# BalanceCar.net
KiCad netlist of a schematic drawn in Altium Designer
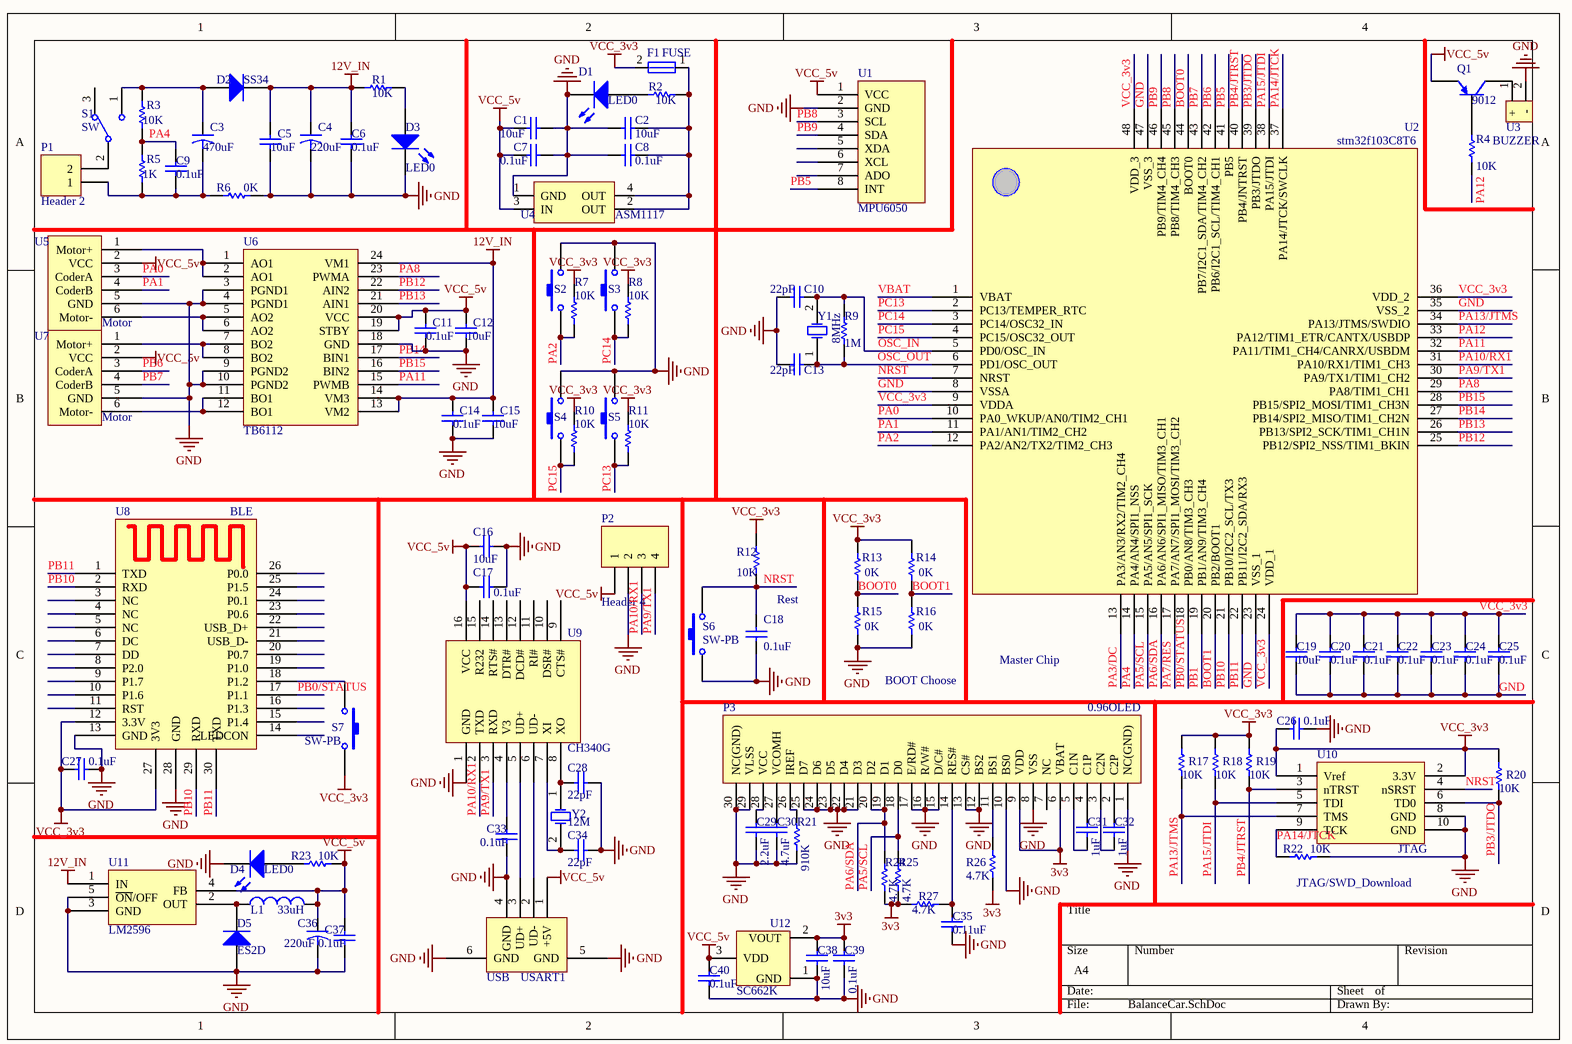
[diagram p0: BalanceCar.SchDoc]

(export (version "E")
  (design (tool "Eeschema 10.0.6"))
  (components
    (comp (ref "C1")
      (value "10uF")
      (footprint "0805")
      (description "Capacitor")
      (fields (field (name "PUBLISHER") "Altium Limited"))
      (libsource (lib "Miscellaneous Devices") (part "Cap"))
    )
    (comp (ref "C2")
      (value "10uF")
      (footprint "0805")
      (description "Capacitor")
      (fields (field (name "PUBLISHER") "Altium Limited"))
      (libsource (lib "Miscellaneous Devices") (part "Cap"))
    )
    (comp (ref "C3")
      (value "470uF")
      (footprint "SMD_8*10.5")
      (description "Capacitor")
      (fields (field (name "PUBLISHER") "Altium Limited"))
      (libsource (lib "Miscellaneous Devices") (part "Cap2"))
    )
    (comp (ref "C4")
      (value "220uF")
      (footprint "SMD_8*10.5")
      (description "Capacitor")
      (fields (field (name "PUBLISHER") "Altium Limited"))
      (libsource (lib "Miscellaneous Devices") (part "Cap2"))
    )
    (comp (ref "C5")
      (value "10uF")
      (footprint "0805")
      (description "Capacitor")
      (fields (field (name "PUBLISHER") "Altium Limited"))
      (libsource (lib "Miscellaneous Devices") (part "Cap"))
    )
    (comp (ref "C6")
      (value "0.1uF")
      (footprint "0603")
      (description "Capacitor")
      (fields (field (name "PUBLISHER") "Altium Limited"))
      (libsource (lib "Miscellaneous Devices") (part "Cap"))
    )
    (comp (ref "C7")
      (value "0.1uF")
      (footprint "0603")
      (description "Capacitor")
      (fields (field (name "PUBLISHER") "Altium Limited"))
      (libsource (lib "Miscellaneous Devices") (part "Cap"))
    )
    (comp (ref "C8")
      (value "0.1uF")
      (footprint "0603")
      (description "Capacitor")
      (fields (field (name "PUBLISHER") "Altium Limited"))
      (libsource (lib "Miscellaneous Devices") (part "Cap"))
    )
    (comp (ref "C9")
      (value "0.1uF")
      (footprint "0603")
      (description "Capacitor")
      (fields (field (name "PUBLISHER") "Altium Limited"))
      (libsource (lib "Miscellaneous Devices") (part "Cap"))
    )
    (comp (ref "C10")
      (value "22pF")
      (footprint "0603")
      (description "Capacitor")
      (fields (field (name "PUBLISHER") "Altium Limited"))
      (libsource (lib "Miscellaneous Devices") (part "Cap"))
    )
    (comp (ref "C11")
      (value "0.1uF")
      (footprint "0603")
      (description "Capacitor")
      (fields (field (name "PUBLISHER") "Altium Limited"))
      (libsource (lib "Miscellaneous Devices") (part "Cap"))
    )
    (comp (ref "C12")
      (value "10uF")
      (footprint "0805")
      (description "Capacitor")
      (fields (field (name "PUBLISHER") "Altium Limited"))
      (libsource (lib "Miscellaneous Devices") (part "Cap"))
    )
    (comp (ref "C13")
      (value "22pF")
      (footprint "0603")
      (description "Capacitor")
      (fields (field (name "PUBLISHER") "Altium Limited"))
      (libsource (lib "Miscellaneous Devices") (part "Cap"))
    )
    (comp (ref "C14")
      (value "0.1uF")
      (footprint "0603")
      (description "Capacitor")
      (fields (field (name "PUBLISHER") "Altium Limited"))
      (libsource (lib "Miscellaneous Devices") (part "Cap"))
    )
    (comp (ref "C15")
      (value "10uF")
      (footprint "0805")
      (description "Capacitor")
      (fields (field (name "PUBLISHER") "Altium Limited"))
      (libsource (lib "Miscellaneous Devices") (part "Cap"))
    )
    (comp (ref "C16")
      (value "10uF")
      (footprint "0805")
      (description "Capacitor")
      (fields (field (name "PUBLISHER") "Altium Limited"))
      (libsource (lib "Miscellaneous Devices") (part "Cap"))
    )
    (comp (ref "C17")
      (value "0.1uF")
      (footprint "0603")
      (description "Capacitor")
      (fields (field (name "PUBLISHER") "Altium Limited"))
      (libsource (lib "Miscellaneous Devices") (part "Cap"))
    )
    (comp (ref "C18")
      (value "0.1uF")
      (footprint "0603")
      (description "Capacitor")
      (fields (field (name "PUBLISHER") "Altium Limited"))
      (libsource (lib "Miscellaneous Devices") (part "Cap"))
    )
    (comp (ref "C19")
      (value "10uF")
      (footprint "0805")
      (description "Capacitor")
      (fields (field (name "PUBLISHER") "Altium Limited"))
      (libsource (lib "Miscellaneous Devices") (part "Cap"))
    )
    (comp (ref "C20")
      (value "0.1uF")
      (footprint "0603")
      (description "Capacitor")
      (fields (field (name "PUBLISHER") "Altium Limited"))
      (libsource (lib "Miscellaneous Devices") (part "Cap"))
    )
    (comp (ref "C21")
      (value "0.1uF")
      (footprint "0603")
      (description "Capacitor")
      (fields (field (name "PUBLISHER") "Altium Limited"))
      (libsource (lib "Miscellaneous Devices") (part "Cap"))
    )
    (comp (ref "C22")
      (value "0.1uF")
      (footprint "0603")
      (description "Capacitor")
      (fields (field (name "PUBLISHER") "Altium Limited"))
      (libsource (lib "Miscellaneous Devices") (part "Cap"))
    )
    (comp (ref "C23")
      (value "0.1uF")
      (footprint "0603")
      (description "Capacitor")
      (fields (field (name "PUBLISHER") "Altium Limited"))
      (libsource (lib "Miscellaneous Devices") (part "Cap"))
    )
    (comp (ref "C24")
      (value "0.1uF")
      (footprint "0603")
      (description "Capacitor")
      (fields (field (name "PUBLISHER") "Altium Limited"))
      (libsource (lib "Miscellaneous Devices") (part "Cap"))
    )
    (comp (ref "C25")
      (value "0.1uF")
      (footprint "0603")
      (description "Capacitor")
      (fields (field (name "PUBLISHER") "Altium Limited"))
      (libsource (lib "Miscellaneous Devices") (part "Cap"))
    )
    (comp (ref "C26")
      (value "0.1uF")
      (footprint "0603")
      (description "Capacitor")
      (fields (field (name "PUBLISHER") "Altium Limited"))
      (libsource (lib "Miscellaneous Devices") (part "Cap"))
    )
    (comp (ref "C27")
      (value "0.1uF")
      (footprint "0603")
      (description "Capacitor")
      (fields (field (name "PUBLISHER") "Altium Limited"))
      (libsource (lib "Miscellaneous Devices") (part "Cap"))
    )
    (comp (ref "C28")
      (value "22pF")
      (footprint "0603")
      (description "Capacitor")
      (fields (field (name "PUBLISHER") "Altium Limited"))
      (libsource (lib "Miscellaneous Devices") (part "Cap"))
    )
    (comp (ref "C29")
      (value "2.2uF")
      (footprint "0603")
      (description "Capacitor")
      (fields (field (name "PUBLISHER") "Altium Limited"))
      (libsource (lib "Miscellaneous Devices") (part "Cap"))
    )
    (comp (ref "C30")
      (value "4.7uF")
      (footprint "0603")
      (description "Capacitor")
      (fields (field (name "PUBLISHER") "Altium Limited"))
      (libsource (lib "Miscellaneous Devices") (part "Cap"))
    )
    (comp (ref "C31")
      (value "1uF")
      (footprint "0603")
      (description "Capacitor")
      (fields (field (name "PUBLISHER") "Altium Limited"))
      (libsource (lib "Miscellaneous Devices") (part "Cap"))
    )
    (comp (ref "C32")
      (value "1uF")
      (footprint "0603")
      (description "Capacitor")
      (fields (field (name "PUBLISHER") "Altium Limited"))
      (libsource (lib "Miscellaneous Devices") (part "Cap"))
    )
    (comp (ref "C33")
      (value "0.1uF")
      (footprint "0603")
      (description "Capacitor")
      (fields (field (name "PUBLISHER") "Altium Limited"))
      (libsource (lib "Miscellaneous Devices") (part "Cap"))
    )
    (comp (ref "C34")
      (value "22pF")
      (footprint "0603")
      (description "Capacitor")
      (fields (field (name "PUBLISHER") "Altium Limited"))
      (libsource (lib "Miscellaneous Devices") (part "Cap"))
    )
    (comp (ref "C35")
      (value "0.11uF")
      (footprint "0603")
      (description "Capacitor")
      (fields (field (name "PUBLISHER") "Altium Limited"))
      (libsource (lib "Miscellaneous Devices") (part "Cap"))
    )
    (comp (ref "C36")
      (value "220uF")
      (footprint "SMD_8*10.5")
      (description "Capacitor")
      (fields (field (name "PUBLISHER") "Altium Limited"))
      (libsource (lib "Miscellaneous Devices") (part "Cap2"))
    )
    (comp (ref "C37")
      (value "0.1uF")
      (footprint "0603")
      (description "Capacitor")
      (fields (field (name "PUBLISHER") "Altium Limited"))
      (libsource (lib "Miscellaneous Devices") (part "Cap"))
    )
    (comp (ref "C38")
      (value "10uF")
      (footprint "0805")
      (description "Capacitor")
      (fields (field (name "PUBLISHER") "Altium Limited"))
      (libsource (lib "Miscellaneous Devices") (part "Cap"))
    )
    (comp (ref "C39")
      (value "0.1uF")
      (footprint "0603")
      (description "Capacitor")
      (fields (field (name "PUBLISHER") "Altium Limited"))
      (libsource (lib "Miscellaneous Devices") (part "Cap"))
    )
    (comp (ref "C40")
      (value "0.1uF")
      (footprint "0603")
      (description "Capacitor")
      (fields (field (name "PUBLISHER") "Altium Limited"))
      (libsource (lib "Miscellaneous Devices") (part "Cap"))
    )
    (comp (ref "D1")
      (value "LED0")
      (footprint "LED")
      (description "Typical INFRARED GaAs LED")
      (fields (field (name "PUBLISHER") "Altium Limited"))
      (libsource (lib "Miscellaneous Devices") (part "LED0"))
    )
    (comp (ref "D2")
      (value "SS34")
      (footprint "SMA")
      (description "1 Amp General Purpose Rectifier")
      (fields (field (name "PUBLISHER") "Altium Limited"))
      (libsource (lib "Miscellaneous Devices") (part "Diode 1N4001"))
    )
    (comp (ref "D3")
      (value "LED0")
      (footprint "LED")
      (description "Typical INFRARED GaAs LED")
      (fields (field (name "PUBLISHER") "Altium Limited"))
      (libsource (lib "Miscellaneous Devices") (part "LED0"))
    )
    (comp (ref "D4")
      (value "LED0")
      (footprint "LED")
      (description "Typical INFRARED GaAs LED")
      (fields (field (name "PUBLISHER") "Altium Limited"))
      (libsource (lib "Miscellaneous Devices") (part "LED0"))
    )
    (comp (ref "D5")
      (value "ES2D")
      (footprint "SMA")
      (description "High Conductance Fast Diode")
      (fields (field (name "PUBLISHER") "Altium Limited"))
      (libsource (lib "Miscellaneous Devices") (part "Diode 1N914"))
    )
    (comp (ref "F1") (value "FUSE") (footprint "1206") (libsource (lib "BalanceCar") (part "FUSE")))
    (comp (ref "L1")
      (value "33uH")
      (footprint "CD54")
      (description "Inductor")
      (fields (field (name "PUBLISHER") "Altium Limited"))
      (libsource (lib "Miscellaneous Devices") (part "Inductor"))
    )
    (comp (ref "P1")
      (value "Header 2")
      (footprint "T")
      (description "Header, 2-Pin")
      (fields (field (name "PUBLISHER") "Altium Limited"))
      (libsource (lib "Miscellaneous Connectors") (part "Header 2"))
    )
    (comp (ref "P2")
      (value "Header 4")
      (footprint "HEADER 4PIN 2.54mm")
      (description "Header, 4-Pin")
      (fields (field (name "PUBLISHER") "Altium Limited"))
      (libsource (lib "Miscellaneous Connectors") (part "Header 4"))
    )
    (comp (ref "P3")
      (value "0.96OLED")
      (footprint "OLED")
      (description "接口")
      (fields (field (name "PUBLISHER") "Altium Limited"))
      (libsource (lib "HLW8012-Demo") (part "0.96OLED"))
    )
    (comp (ref "Q1")
      (value "9012")
      (footprint "SOP23")
      (description "PNP Bipolar Transistor")
      (fields (field (name "PUBLISHER") "Altium Limited"))
      (libsource (lib "Miscellaneous Devices") (part "PNP"))
    )
    (comp (ref "R1")
      (value "10K")
      (footprint "RES")
      (description "Resistor")
      (fields (field (name "PUBLISHER") "Altium Limited"))
      (libsource (lib "Miscellaneous Devices") (part "Res1"))
    )
    (comp (ref "R2")
      (value "10K")
      (footprint "RES")
      (description "Resistor")
      (fields (field (name "PUBLISHER") "Altium Limited"))
      (libsource (lib "Miscellaneous Devices") (part "Res1"))
    )
    (comp (ref "R3")
      (value "10K")
      (footprint "RES")
      (description "Resistor")
      (fields (field (name "PUBLISHER") "Altium Limited"))
      (libsource (lib "Miscellaneous Devices") (part "Res1"))
    )
    (comp (ref "R4")
      (value "10K")
      (footprint "RES")
      (description "Resistor")
      (fields (field (name "PUBLISHER") "Altium Limited"))
      (libsource (lib "Miscellaneous Devices") (part "Res1"))
    )
    (comp (ref "R5")
      (value "1K")
      (footprint "RES")
      (description "Resistor")
      (fields (field (name "PUBLISHER") "Altium Limited"))
      (libsource (lib "Miscellaneous Devices") (part "Res1"))
    )
    (comp (ref "R6")
      (value "0K")
      (footprint "RES")
      (description "Resistor")
      (fields (field (name "PUBLISHER") "Altium Limited"))
      (libsource (lib "Miscellaneous Devices") (part "Res1"))
    )
    (comp (ref "R7")
      (value "10K")
      (footprint "RES")
      (description "Resistor")
      (fields (field (name "PUBLISHER") "Altium Limited"))
      (libsource (lib "Miscellaneous Devices") (part "Res1"))
    )
    (comp (ref "R8")
      (value "10K")
      (footprint "RES")
      (description "Resistor")
      (fields (field (name "PUBLISHER") "Altium Limited"))
      (libsource (lib "Miscellaneous Devices") (part "Res1"))
    )
    (comp (ref "R9")
      (value "1M")
      (footprint "RES")
      (description "Resistor")
      (fields (field (name "PUBLISHER") "Altium Limited"))
      (libsource (lib "Miscellaneous Devices") (part "Res1"))
    )
    (comp (ref "R10")
      (value "10K")
      (footprint "RES")
      (description "Resistor")
      (fields (field (name "PUBLISHER") "Altium Limited"))
      (libsource (lib "Miscellaneous Devices") (part "Res1"))
    )
    (comp (ref "R11")
      (value "10K")
      (footprint "RES")
      (description "Resistor")
      (fields (field (name "PUBLISHER") "Altium Limited"))
      (libsource (lib "Miscellaneous Devices") (part "Res1"))
    )
    (comp (ref "R12")
      (value "10K")
      (footprint "RES")
      (description "Resistor")
      (fields (field (name "PUBLISHER") "Altium Limited"))
      (libsource (lib "Miscellaneous Devices") (part "Res1"))
    )
    (comp (ref "R13")
      (value "0K")
      (footprint "RES")
      (description "Resistor")
      (fields (field (name "PUBLISHER") "Altium Limited"))
      (libsource (lib "Miscellaneous Devices") (part "Res1"))
    )
    (comp (ref "R14")
      (value "0K")
      (footprint "RES")
      (description "Resistor")
      (fields (field (name "PUBLISHER") "Altium Limited"))
      (libsource (lib "Miscellaneous Devices") (part "Res1"))
    )
    (comp (ref "R15")
      (value "0K")
      (footprint "RES")
      (description "Resistor")
      (fields (field (name "PUBLISHER") "Altium Limited"))
      (libsource (lib "Miscellaneous Devices") (part "Res1"))
    )
    (comp (ref "R16")
      (value "0K")
      (footprint "RES")
      (description "Resistor")
      (fields (field (name "PUBLISHER") "Altium Limited"))
      (libsource (lib "Miscellaneous Devices") (part "Res1"))
    )
    (comp (ref "R17")
      (value "10K")
      (footprint "RES")
      (description "Resistor")
      (fields (field (name "PUBLISHER") "Altium Limited"))
      (libsource (lib "Miscellaneous Devices") (part "Res1"))
    )
    (comp (ref "R18")
      (value "10K")
      (footprint "RES")
      (description "Resistor")
      (fields (field (name "PUBLISHER") "Altium Limited"))
      (libsource (lib "Miscellaneous Devices") (part "Res1"))
    )
    (comp (ref "R19")
      (value "10K")
      (footprint "RES")
      (description "Resistor")
      (fields (field (name "PUBLISHER") "Altium Limited"))
      (libsource (lib "Miscellaneous Devices") (part "Res1"))
    )
    (comp (ref "R20")
      (value "10K")
      (footprint "RES")
      (description "Resistor")
      (fields (field (name "PUBLISHER") "Altium Limited"))
      (libsource (lib "Miscellaneous Devices") (part "Res1"))
    )
    (comp (ref "R21")
      (value "910K")
      (footprint "RES")
      (description "Resistor")
      (fields (field (name "PUBLISHER") "Altium Limited"))
      (libsource (lib "Miscellaneous Devices") (part "Res1"))
    )
    (comp (ref "R22")
      (value "10K")
      (footprint "RES")
      (description "Resistor")
      (fields (field (name "PUBLISHER") "Altium Limited"))
      (libsource (lib "Miscellaneous Devices") (part "Res1"))
    )
    (comp (ref "R23")
      (value "10K")
      (footprint "RES")
      (description "Resistor")
      (fields (field (name "PUBLISHER") "Altium Limited"))
      (libsource (lib "Miscellaneous Devices") (part "Res1"))
    )
    (comp (ref "R24")
      (value "4.7K")
      (footprint "RES")
      (description "Resistor")
      (fields (field (name "PUBLISHER") "Altium Limited"))
      (libsource (lib "Miscellaneous Devices") (part "Res1"))
    )
    (comp (ref "R25")
      (value "4.7K")
      (footprint "RES")
      (description "Resistor")
      (fields (field (name "PUBLISHER") "Altium Limited"))
      (libsource (lib "Miscellaneous Devices") (part "Res1"))
    )
    (comp (ref "R26")
      (value "4.7K")
      (footprint "RES")
      (description "Resistor")
      (fields (field (name "PUBLISHER") "Altium Limited"))
      (libsource (lib "Miscellaneous Devices") (part "Res1"))
    )
    (comp (ref "R27")
      (value "4.7K")
      (footprint "RES")
      (description "Resistor")
      (fields (field (name "PUBLISHER") "Altium Limited"))
      (libsource (lib "Miscellaneous Devices") (part "Res1"))
    )
    (comp (ref "S1")
      (value "SW")
      (footprint "MTS102")
      (description "SPDT Subminiature Toggle Switch, Right Angle Mounting, Vertical Actuation")
      (fields (field (name "PUBLISHER") "Altium Limited"))
      (libsource (lib "Miscellaneous Devices") (part "SW-SPDT"))
    )
    (comp (ref "S2")
      (value "~")
      (footprint "KEY_SOT_P2")
      (description "Switch")
      (fields (field (name "PUBLISHER") "Altium Limited"))
      (libsource (lib "Miscellaneous Devices") (part "SW-PB"))
    )
    (comp (ref "S3")
      (value "~")
      (footprint "KEY_SOT_P2")
      (description "Switch")
      (fields (field (name "PUBLISHER") "Altium Limited"))
      (libsource (lib "Miscellaneous Devices") (part "SW-PB"))
    )
    (comp (ref "S4")
      (value "~")
      (footprint "KEY_SOT_P2")
      (description "Switch")
      (fields (field (name "PUBLISHER") "Altium Limited"))
      (libsource (lib "Miscellaneous Devices") (part "SW-PB"))
    )
    (comp (ref "S5")
      (value "~")
      (footprint "KEY_SOT_P2")
      (description "Switch")
      (fields (field (name "PUBLISHER") "Altium Limited"))
      (libsource (lib "Miscellaneous Devices") (part "SW-PB"))
    )
    (comp (ref "S6")
      (value "SW-PB")
      (footprint "KEY_SOT_P2")
      (description "Switch")
      (fields (field (name "PUBLISHER") "Altium Limited"))
      (libsource (lib "Miscellaneous Devices") (part "SW-PB"))
    )
    (comp (ref "S7")
      (value "SW-PB")
      (footprint "KEY_SOT_P2")
      (description "Switch")
      (fields (field (name "PUBLISHER") "Altium Limited"))
      (libsource (lib "Miscellaneous Devices") (part "SW-PB"))
    )
    (comp (ref "U1") (value "MPU6050") (footprint "MPU6050") (libsource (lib "BalanceCar") (part "MPU6050")))
    (comp (ref "U2")
      (value "stm32f103C8T6")
      (footprint "LQFP48")
      (libsource (lib "BalanceCar") (part "stm32f103C8T6"))
    )
    (comp (ref "U3") (value "BUZZER") (footprint "BUZZER") (libsource (lib "BalanceCar") (part "BUZZER")))
    (comp (ref "U4") (value "ASM1117") (footprint "SOT-223") (libsource (lib "BalanceCar") (part "ASM1117")))
    (comp (ref "U5") (value "Motor") (footprint "Motor") (libsource (lib "BalanceCar") (part "Motor")))
    (comp (ref "U6") (value "TB6112") (footprint "SSOP24") (libsource (lib "BalanceCar") (part "TB6112")))
    (comp (ref "U7") (value "Motor") (footprint "Motor") (libsource (lib "BalanceCar") (part "Motor")))
    (comp (ref "U8") (value "BLE") (footprint "BLUETOOTH") (libsource (lib "BalanceCar") (part "BLE")))
    (comp (ref "U9") (value "CH340G") (footprint "SOP-16") (libsource (lib "Schlib1") (part "CH340G")))
    (comp (ref "U10")
      (value "JTAG")
      (footprint "HEADER 2x5 2mm")
      (libsource (lib "Boat_CorePCB") (part "JTAG"))
    )
    (comp (ref "U11") (value "LM2596") (footprint "TO263-5") (libsource (lib "BalanceCar") (part "LM2596")))
    (comp (ref "U12") (value "SC662K") (footprint "SOP23") (libsource (lib "BalanceCar") (part "SC662K")))
    (comp (ref "USART1") (value "USB") (footprint "Micro_USB") (libsource (lib "Schlib1") (part "USB")))
    (comp (ref "Y1")
      (value "8MHz")
      (footprint "HC-49S")
      (description "Crystal Oscillator")
      (fields (field (name "PUBLISHER") "Altium Limited"))
      (libsource (lib "Miscellaneous Devices") (part "XTAL"))
    )
    (comp (ref "Y2")
      (value "12M")
      (footprint "HC-49S")
      (description "Crystal Oscillator")
      (fields (field (name "PUBLISHER") "Altium Limited"))
      (libsource (lib "Miscellaneous Devices") (part "XTAL"))
    )
  )
  (nets
    (net (code "1") (name "/BOOT0") (class "Default")
      (node (ref "R13") (pin "1") (pinfunction "1_1") (pintype "passive"))
      (node (ref "R15") (pin "2") (pinfunction "2_2") (pintype "passive"))
      (node (ref "U2") (pin "44") (pinfunction "BOOT0_44") (pintype "passive"))
    )
    (net (code "2") (name "/BOOT1") (class "Default")
      (node (ref "R14") (pin "1") (pinfunction "1_1") (pintype "passive"))
      (node (ref "R16") (pin "2") (pinfunction "2_2") (pintype "passive"))
      (node (ref "U2") (pin "20") (pinfunction "PB2/BOOT1_20") (pintype "passive"))
    )
    (net (code "3") (name "/NRST") (class "Default")
      (node (ref "C18") (pin "2") (pinfunction "2_2") (pintype "passive"))
      (node (ref "R12") (pin "1") (pinfunction "1_1") (pintype "passive"))
      (node (ref "S6") (pin "2") (pinfunction "2_2") (pintype "passive"))
      (node (ref "U10") (pin "4") (pinfunction "nSRST_4") (pintype "passive"))
      (node (ref "U2") (pin "7") (pinfunction "NRST_7") (pintype "passive"))
    )
    (net (code "4") (name "/OSC_IN") (class "Default")
      (node (ref "C10") (pin "2") (pinfunction "2_2") (pintype "passive"))
      (node (ref "R9") (pin "2") (pinfunction "2_2") (pintype "passive"))
      (node (ref "U2") (pin "5") (pinfunction "PD0/OSC_IN_5") (pintype "passive"))
      (node (ref "Y1") (pin "2") (pinfunction "OSC2_2") (pintype "passive"))
    )
    (net (code "5") (name "/OSC_OUT") (class "Default")
      (node (ref "C13") (pin "2") (pinfunction "2_2") (pintype "passive"))
      (node (ref "R9") (pin "1") (pinfunction "1_1") (pintype "passive"))
      (node (ref "U2") (pin "6") (pinfunction "PD1/OSC_OUT_6") (pintype "passive"))
      (node (ref "Y1") (pin "1") (pinfunction "OSC1_1") (pintype "passive"))
    )
    (net (code "6") (name "/PA0") (class "Default")
      (node (ref "U2") (pin "10") (pinfunction "PA0_WKUP/AN0/TIM2_CH1_10") (pintype "passive"))
      (node (ref "U5") (pin "3") (pinfunction "CoderA_3") (pintype "passive"))
    )
    (net (code "7") (name "/PA1") (class "Default")
      (node (ref "U2") (pin "11") (pinfunction "PA1/AN1/TIM2_CH2_11") (pintype "passive"))
      (node (ref "U5") (pin "4") (pinfunction "CoderB_4") (pintype "passive"))
    )
    (net (code "8") (name "/PA2") (class "Default")
      (node (ref "R7") (pin "1") (pinfunction "1_1") (pintype "passive"))
      (node (ref "S2") (pin "1") (pinfunction "1_1") (pintype "passive"))
      (node (ref "U2") (pin "12") (pinfunction "PA2/AN2/TX2/TIM2_CH3_12") (pintype "passive"))
    )
    (net (code "9") (name "/PA3{slash}DC") (class "Default")
      (node (ref "U2") (pin "13") (pinfunction "PA3/AN3/RX2/TIM2_CH4_13") (pintype "passive"))
    )
    (net (code "10") (name "/PA4") (class "Default")
      (node (ref "C9") (pin "2") (pinfunction "2_2") (pintype "passive"))
      (node (ref "R3") (pin "1") (pinfunction "1_1") (pintype "passive"))
      (node (ref "R5") (pin "2") (pinfunction "2_2") (pintype "passive"))
      (node (ref "U2") (pin "14") (pinfunction "PA4/AN4/SPI1_NSS_14") (pintype "passive"))
    )
    (net (code "11") (name "/PA5{slash}SCL") (class "Default")
      (node (ref "P3") (pin "18") (pinfunction "D0_18") (pintype "passive"))
      (node (ref "R25") (pin "1") (pinfunction "1_1") (pintype "passive"))
      (node (ref "U2") (pin "15") (pinfunction "PA5/AN5/SPI1_SCK_15") (pintype "passive"))
    )
    (net (code "12") (name "/PA6{slash}SDA") (class "Default")
      (node (ref "P3") (pin "19") (pinfunction "D1_19") (pintype "passive"))
      (node (ref "P3") (pin "20") (pinfunction "D2_20") (pintype "passive"))
      (node (ref "R24") (pin "1") (pinfunction "1_1") (pintype "passive"))
      (node (ref "U2") (pin "16") (pinfunction "PA6/AN6/SPI1_MISO/TIM3_CH1_16") (pintype "passive"))
    )
    (net (code "13") (name "/PA7{slash}RES") (class "Default")
      (node (ref "U2") (pin "17") (pinfunction "PA7/AN7/SPI1_MOSI/TIM3_CH2_17") (pintype "passive"))
    )
    (net (code "14") (name "/PA8") (class "Default")
      (node (ref "U2") (pin "29") (pinfunction "PA8/TIM1_CH1_29") (pintype "passive"))
      (node (ref "U6") (pin "23") (pinfunction "PWMA_23") (pintype "passive"))
    )
    (net (code "15") (name "/PA9{slash}TX1") (class "Default")
      (node (ref "P2") (pin "4") (pinfunction "4_4") (pintype "passive"))
      (node (ref "U2") (pin "30") (pinfunction "PA9/TX1/TIM1_CH2_30") (pintype "passive"))
      (node (ref "U9") (pin "3") (pinfunction "RXD_3") (pintype "passive"))
    )
    (net (code "16") (name "/PA10{slash}RX1") (class "Default")
      (node (ref "P2") (pin "3") (pinfunction "3_3") (pintype "passive"))
      (node (ref "U2") (pin "31") (pinfunction "PA10/RX1/TIM1_CH3_31") (pintype "passive"))
      (node (ref "U9") (pin "2") (pinfunction "TXD_2") (pintype "passive"))
    )
    (net (code "17") (name "/PA11") (class "Default")
      (node (ref "U2") (pin "32") (pinfunction "PA11/TIM1_CH4/CANRX/USBDM_32") (pintype "passive"))
      (node (ref "U6") (pin "15") (pinfunction "PWMB_15") (pintype "passive"))
    )
    (net (code "18") (name "/PA12") (class "Default")
      (node (ref "R4") (pin "1") (pinfunction "1_1") (pintype "passive"))
      (node (ref "U2") (pin "33") (pinfunction "PA12/TIM1_ETR/CANTX/USBDP_33") (pintype "passive"))
    )
    (net (code "19") (name "/PA13{slash}JTMS") (class "Default")
      (node (ref "R17") (pin "1") (pinfunction "1_1") (pintype "passive"))
      (node (ref "U10") (pin "7") (pinfunction "TMS_7") (pintype "passive"))
      (node (ref "U2") (pin "34") (pinfunction "PA13/JTMS/SWDIO_34") (pintype "passive"))
    )
    (net (code "20") (name "/PA14{slash}JTCK") (class "Default")
      (node (ref "R22") (pin "2") (pinfunction "2_2") (pintype "passive"))
      (node (ref "U10") (pin "9") (pinfunction "TCK_9") (pintype "passive"))
      (node (ref "U2") (pin "37") (pinfunction "PA14/JTCK/SWCLK_37") (pintype "passive"))
    )
    (net (code "21") (name "/PA15{slash}JTDI") (class "Default")
      (node (ref "R18") (pin "1") (pinfunction "1_1") (pintype "passive"))
      (node (ref "U10") (pin "5") (pinfunction "TDI_5") (pintype "passive"))
      (node (ref "U2") (pin "38") (pinfunction "PA15/JTDI_38") (pintype "passive"))
    )
    (net (code "22") (name "/PB0{slash}STATUS") (class "Default")
      (node (ref "U2") (pin "18") (pinfunction "PB0/AN8/TIM3_CH3_18") (pintype "passive"))
      (node (ref "U8") (pin "17") (pinfunction "P1.1_17") (pintype "passive"))
    )
    (net (code "23") (name "/PB1") (class "Default")
      (node (ref "U2") (pin "19") (pinfunction "PB1/AN9/TIM3_CH4_19") (pintype "passive"))
    )
    (net (code "24") (name "/PB3{slash}JTDO") (class "Default")
      (node (ref "R20") (pin "1") (pinfunction "1_1") (pintype "passive"))
      (node (ref "U10") (pin "6") (pinfunction "TD0_6") (pintype "passive"))
      (node (ref "U2") (pin "39") (pinfunction "PB3/JTDO_39") (pintype "passive"))
    )
    (net (code "25") (name "/PB4{slash}JTRST") (class "Default")
      (node (ref "R19") (pin "1") (pinfunction "1_1") (pintype "passive"))
      (node (ref "U10") (pin "3") (pinfunction "nTRST_3") (pintype "passive"))
      (node (ref "U2") (pin "40") (pinfunction "PB4/JNTRST_40") (pintype "passive"))
    )
    (net (code "26") (name "/PB5") (class "Default")
      (node (ref "U1") (pin "8") (pinfunction "INT_8") (pintype "passive"))
      (node (ref "U2") (pin "41") (pinfunction "PB5_41") (pintype "passive"))
    )
    (net (code "27") (name "/PB6") (class "Default")
      (node (ref "U2") (pin "42") (pinfunction "PB6/I2C1_SCL/TIM4_CH1_42") (pintype "passive"))
      (node (ref "U7") (pin "3") (pinfunction "CoderA_3") (pintype "passive"))
    )
    (net (code "28") (name "/PB7") (class "Default")
      (node (ref "U2") (pin "43") (pinfunction "PB7/I2C1_SDA/TIM4_CH2_43") (pintype "passive"))
      (node (ref "U7") (pin "4") (pinfunction "CoderB_4") (pintype "passive"))
    )
    (net (code "29") (name "/PB8") (class "Default")
      (node (ref "U1") (pin "3") (pinfunction "SCL_3") (pintype "passive"))
      (node (ref "U2") (pin "45") (pinfunction "PB8/TIM4_CH3_45") (pintype "passive"))
    )
    (net (code "30") (name "/PB9") (class "Default")
      (node (ref "U1") (pin "4") (pinfunction "SDA_4") (pintype "passive"))
      (node (ref "U2") (pin "46") (pinfunction "PB9/TIM4_CH4_46") (pintype "passive"))
    )
    (net (code "31") (name "/PB10") (class "Default")
      (node (ref "U2") (pin "21") (pinfunction "PB10/I2C2_SCL/TX3_21") (pintype "passive"))
      (node (ref "U8") (pin "2") (pinfunction "RXD_2") (pintype "passive"))
      (node (ref "U8") (pin "29") (pinfunction "RXD_29") (pintype "passive"))
    )
    (net (code "32") (name "/PB11") (class "Default")
      (node (ref "U2") (pin "22") (pinfunction "PB11/I2C2_SDA/RX3_22") (pintype "passive"))
      (node (ref "U8") (pin "1") (pinfunction "TXD_1") (pintype "passive"))
      (node (ref "U8") (pin "30") (pinfunction "TXD_30") (pintype "passive"))
    )
    (net (code "33") (name "/PB12") (class "Default")
      (node (ref "U2") (pin "25") (pinfunction "PB12/SPI2_NSS/TIM1_BKIN_25") (pintype "passive"))
      (node (ref "U6") (pin "22") (pinfunction "AIN2_22") (pintype "passive"))
    )
    (net (code "34") (name "/PB13") (class "Default")
      (node (ref "U2") (pin "26") (pinfunction "PB13/SPI2_SCK/TIM1_CH1N_26") (pintype "passive"))
      (node (ref "U6") (pin "21") (pinfunction "AIN1_21") (pintype "passive"))
    )
    (net (code "35") (name "/PB14") (class "Default")
      (node (ref "U2") (pin "27") (pinfunction "PB14/SPI2_MISO/TIM1_CH2N_27") (pintype "passive"))
      (node (ref "U6") (pin "17") (pinfunction "BIN1_17") (pintype "passive"))
    )
    (net (code "36") (name "/PB15") (class "Default")
      (node (ref "U2") (pin "28") (pinfunction "PB15/SPI2_MOSI/TIM1_CH3N_28") (pintype "passive"))
      (node (ref "U6") (pin "16") (pinfunction "BIN2_16") (pintype "passive"))
    )
    (net (code "37") (name "/PC13") (class "Default")
      (node (ref "R11") (pin "1") (pinfunction "1_1") (pintype "passive"))
      (node (ref "S5") (pin "1") (pinfunction "1_1") (pintype "passive"))
      (node (ref "U2") (pin "2") (pinfunction "PC13/TEMPER_RTC_2") (pintype "passive"))
    )
    (net (code "38") (name "/PC14") (class "Default")
      (node (ref "R8") (pin "1") (pinfunction "1_1") (pintype "passive"))
      (node (ref "S3") (pin "1") (pinfunction "1_1") (pintype "passive"))
      (node (ref "U2") (pin "3") (pinfunction "PC14/OSC32_IN_3") (pintype "passive"))
    )
    (net (code "39") (name "/PC15") (class "Default")
      (node (ref "R10") (pin "1") (pinfunction "1_1") (pintype "passive"))
      (node (ref "S4") (pin "1") (pinfunction "1_1") (pintype "passive"))
      (node (ref "U2") (pin "4") (pinfunction "PC15/OSC32_OUT_4") (pintype "passive"))
    )
    (net (code "40") (name "/VBAT") (class "Default")
      (node (ref "U2") (pin "1") (pinfunction "VBAT_1") (pintype "passive"))
    )
    (net (code "41") (name "3v3") (class "Default")
      (node (ref "C38") (pin "2") (pinfunction "2_2") (pintype "passive"))
      (node (ref "C39") (pin "2") (pinfunction "2_2") (pintype "passive"))
      (node (ref "P3") (pin "6") (pinfunction "VBAT_6") (pintype "passive"))
      (node (ref "P3") (pin "9") (pinfunction "VDD_9") (pintype "passive"))
      (node (ref "R24") (pin "2") (pinfunction "2_2") (pintype "passive"))
      (node (ref "R25") (pin "2") (pinfunction "2_2") (pintype "passive"))
      (node (ref "R26") (pin "2") (pinfunction "2_2") (pintype "passive"))
      (node (ref "R27") (pin "1") (pinfunction "1_1") (pintype "passive"))
      (node (ref "U12") (pin "2") (pinfunction "VOUT_2") (pintype "passive"))
    )
    (net (code "42") (name "12V_IN") (class "Default")
      (node (ref "C14") (pin "2") (pinfunction "2_2") (pintype "passive"))
      (node (ref "C15") (pin "2") (pinfunction "2_2") (pintype "passive"))
      (node (ref "C4") (pin "1") (pinfunction "1_1") (pintype "passive"))
      (node (ref "C5") (pin "2") (pinfunction "2_2") (pintype "passive"))
      (node (ref "C6") (pin "2") (pinfunction "2_2") (pintype "passive"))
      (node (ref "D2") (pin "2") (pinfunction "K_2") (pintype "passive"))
      (node (ref "R1") (pin "1") (pinfunction "1_1") (pintype "passive"))
      (node (ref "U11") (pin "1") (pinfunction "IN_1") (pintype "passive"))
      (node (ref "U6") (pin "13") (pinfunction "VM2_13") (pintype "passive"))
      (node (ref "U6") (pin "14") (pinfunction "VM3_14") (pintype "passive"))
      (node (ref "U6") (pin "24") (pinfunction "VM1_24") (pintype "passive"))
    )
    (net (code "43") (name "GND") (class "Default")
      (node (ref "C1") (pin "2") (pinfunction "2_2") (pintype "passive"))
      (node (ref "C10") (pin "1") (pinfunction "1_1") (pintype "passive"))
      (node (ref "C11") (pin "1") (pinfunction "1_1") (pintype "passive"))
      (node (ref "C12") (pin "1") (pinfunction "1_1") (pintype "passive"))
      (node (ref "C13") (pin "1") (pinfunction "1_1") (pintype "passive"))
      (node (ref "C14") (pin "1") (pinfunction "1_1") (pintype "passive"))
      (node (ref "C15") (pin "1") (pinfunction "1_1") (pintype "passive"))
      (node (ref "C16") (pin "1") (pinfunction "1_1") (pintype "passive"))
      (node (ref "C17") (pin "1") (pinfunction "1_1") (pintype "passive"))
      (node (ref "C18") (pin "1") (pinfunction "1_1") (pintype "passive"))
      (node (ref "C19") (pin "1") (pinfunction "1_1") (pintype "passive"))
      (node (ref "C2") (pin "1") (pinfunction "1_1") (pintype "passive"))
      (node (ref "C20") (pin "1") (pinfunction "1_1") (pintype "passive"))
      (node (ref "C21") (pin "1") (pinfunction "1_1") (pintype "passive"))
      (node (ref "C22") (pin "1") (pinfunction "1_1") (pintype "passive"))
      (node (ref "C23") (pin "1") (pinfunction "1_1") (pintype "passive"))
      (node (ref "C24") (pin "1") (pinfunction "1_1") (pintype "passive"))
      (node (ref "C25") (pin "1") (pinfunction "1_1") (pintype "passive"))
      (node (ref "C26") (pin "2") (pinfunction "2_2") (pintype "passive"))
      (node (ref "C27") (pin "2") (pinfunction "2_2") (pintype "passive"))
      (node (ref "C28") (pin "1") (pinfunction "1_1") (pintype "passive"))
      (node (ref "C29") (pin "1") (pinfunction "1_1") (pintype "passive"))
      (node (ref "C30") (pin "1") (pinfunction "1_1") (pintype "passive"))
      (node (ref "C33") (pin "1") (pinfunction "1_1") (pintype "passive"))
      (node (ref "C34") (pin "1") (pinfunction "1_1") (pintype "passive"))
      (node (ref "C35") (pin "1") (pinfunction "1_1") (pintype "passive"))
      (node (ref "C36") (pin "2") (pinfunction "2_2") (pintype "passive"))
      (node (ref "C37") (pin "1") (pinfunction "1_1") (pintype "passive"))
      (node (ref "C38") (pin "1") (pinfunction "1_1") (pintype "passive"))
      (node (ref "C39") (pin "1") (pinfunction "1_1") (pintype "passive"))
      (node (ref "C4") (pin "2") (pinfunction "2_2") (pintype "passive"))
      (node (ref "C40") (pin "1") (pinfunction "1_1") (pintype "passive"))
      (node (ref "C5") (pin "1") (pinfunction "1_1") (pintype "passive"))
      (node (ref "C6") (pin "1") (pinfunction "1_1") (pintype "passive"))
      (node (ref "C7") (pin "2") (pinfunction "2_2") (pintype "passive"))
      (node (ref "C8") (pin "1") (pinfunction "1_1") (pintype "passive"))
      (node (ref "D1") (pin "2") (pinfunction "K_2") (pintype "passive"))
      (node (ref "D3") (pin "2") (pinfunction "K_2") (pintype "passive"))
      (node (ref "D4") (pin "2") (pinfunction "K_2") (pintype "passive"))
      (node (ref "D5") (pin "1") (pinfunction "A_1") (pintype "passive"))
      (node (ref "P2") (pin "2") (pinfunction "2_2") (pintype "passive"))
      (node (ref "P3") (pin "1") (pinfunction "NC(GND)_1") (pintype "passive"))
      (node (ref "P3") (pin "10") (pinfunction "BS0_10") (pintype "passive"))
      (node (ref "P3") (pin "12") (pinfunction "BS2_12") (pintype "passive"))
      (node (ref "P3") (pin "13") (pinfunction "CS#_13") (pintype "passive"))
      (node (ref "P3") (pin "15") (pinfunction "D/C#_15") (pintype "passive"))
      (node (ref "P3") (pin "16") (pinfunction "R/W#_16") (pintype "passive"))
      (node (ref "P3") (pin "17") (pinfunction "E/RD#_17") (pintype "passive"))
      (node (ref "P3") (pin "21") (pinfunction "D3_21") (pintype "passive"))
      (node (ref "P3") (pin "22") (pinfunction "D4_22") (pintype "passive"))
      (node (ref "P3") (pin "23") (pinfunction "D5_23") (pintype "passive"))
      (node (ref "P3") (pin "24") (pinfunction "D6_24") (pintype "passive"))
      (node (ref "P3") (pin "25") (pinfunction "D7_25") (pintype "passive"))
      (node (ref "P3") (pin "29") (pinfunction "VLSS_29") (pintype "passive"))
      (node (ref "P3") (pin "30") (pinfunction "NC(GND)_30") (pintype "passive"))
      (node (ref "P3") (pin "8") (pinfunction "VSS_8") (pintype "passive"))
      (node (ref "R15") (pin "1") (pinfunction "1_1") (pintype "passive"))
      (node (ref "R16") (pin "1") (pinfunction "1_1") (pintype "passive"))
      (node (ref "R21") (pin "2") (pinfunction "2_2") (pintype "passive"))
      (node (ref "R22") (pin "1") (pinfunction "1_1") (pintype "passive"))
      (node (ref "R6") (pin "2") (pinfunction "2_2") (pintype "passive"))
      (node (ref "S2") (pin "2") (pinfunction "2_2") (pintype "passive"))
      (node (ref "S3") (pin "2") (pinfunction "2_2") (pintype "passive"))
      (node (ref "S4") (pin "2") (pinfunction "2_2") (pintype "passive"))
      (node (ref "S5") (pin "2") (pinfunction "2_2") (pintype "passive"))
      (node (ref "S6") (pin "1") (pinfunction "1_1") (pintype "passive"))
      (node (ref "U1") (pin "2") (pinfunction "GND_2") (pintype "passive"))
      (node (ref "U10") (pin "10") (pinfunction "GND_10") (pintype "passive"))
      (node (ref "U10") (pin "8") (pinfunction "GND_8") (pintype "passive"))
      (node (ref "U11") (pin "3") (pinfunction "GND_3") (pintype "passive"))
      (node (ref "U11") (pin "5") (pinfunction "~{ON}/OFF_5") (pintype "passive"))
      (node (ref "U12") (pin "1") (pinfunction "GND_1") (pintype "passive"))
      (node (ref "U2") (pin "23") (pinfunction "VSS_1_23") (pintype "passive"))
      (node (ref "U2") (pin "35") (pinfunction "VSS_2_35") (pintype "passive"))
      (node (ref "U2") (pin "47") (pinfunction "VSS_3_47") (pintype "passive"))
      (node (ref "U2") (pin "8") (pinfunction "VSSA_8") (pintype "passive"))
      (node (ref "U3") (pin "2") (pinfunction "-_2") (pintype "passive"))
      (node (ref "U4") (pin "1") (pinfunction "GND_1") (pintype "passive"))
      (node (ref "U5") (pin "5") (pinfunction "GND_5") (pintype "passive"))
      (node (ref "U6") (pin "10") (pinfunction "PGND2_10") (pintype "passive"))
      (node (ref "U6") (pin "18") (pinfunction "GND_18") (pintype "passive"))
      (node (ref "U6") (pin "3") (pinfunction "PGND1_3") (pintype "passive"))
      (node (ref "U6") (pin "4") (pinfunction "PGND1_4") (pintype "passive"))
      (node (ref "U6") (pin "9") (pinfunction "PGND2_9") (pintype "passive"))
      (node (ref "U7") (pin "5") (pinfunction "GND_5") (pintype "passive"))
      (node (ref "U8") (pin "13") (pinfunction "GND_13") (pintype "passive"))
      (node (ref "U8") (pin "28") (pinfunction "GND_28") (pintype "passive"))
      (node (ref "U9") (pin "1") (pinfunction "GND_1") (pintype "passive"))
      (node (ref "USART1") (pin "4") (pinfunction "GND_4") (pintype "passive"))
      (node (ref "USART1") (pin "5") (pinfunction "GND_5") (pintype "passive"))
      (node (ref "USART1") (pin "6") (pinfunction "GND_6") (pintype "passive"))
    )
    (net (code "44") (name "Net-(C2-Pad2)") (class "Default")
      (node (ref "C2") (pin "2") (pinfunction "2_2") (pintype "passive"))
      (node (ref "C8") (pin "2") (pinfunction "2_2") (pintype "passive"))
      (node (ref "F1") (pin "1") (pinfunction "1_1") (pintype "passive"))
      (node (ref "R2") (pin "2") (pinfunction "2_2") (pintype "passive"))
      (node (ref "U4") (pin "2") (pinfunction "OUT_2") (pintype "passive"))
      (node (ref "U4") (pin "4") (pinfunction "OUT_4") (pintype "passive"))
    )
    (net (code "45") (name "Net-(C3-Pad2)") (class "Default")
      (node (ref "C3") (pin "2") (pinfunction "2_2") (pintype "passive"))
      (node (ref "C9") (pin "1") (pinfunction "1_1") (pintype "passive"))
      (node (ref "P1") (pin "1") (pinfunction "1_1") (pintype "passive"))
      (node (ref "R5") (pin "1") (pinfunction "1_1") (pintype "passive"))
      (node (ref "R6") (pin "1") (pinfunction "1_1") (pintype "passive"))
    )
    (net (code "46") (name "Net-(D1-A)") (class "Default")
      (node (ref "D1") (pin "1") (pinfunction "A_1") (pintype "passive"))
      (node (ref "R2") (pin "1") (pinfunction "1_1") (pintype "passive"))
    )
    (net (code "47") (name "Net-(D2-A)") (class "Default")
      (node (ref "C3") (pin "1") (pinfunction "1_1") (pintype "passive"))
      (node (ref "D2") (pin "1") (pinfunction "A_1") (pintype "passive"))
      (node (ref "R3") (pin "2") (pinfunction "2_2") (pintype "passive"))
      (node (ref "S1") (pin "1") (pinfunction "1_1") (pintype "passive"))
    )
    (net (code "48") (name "Net-(D3-A)") (class "Default")
      (node (ref "D3") (pin "1") (pinfunction "A_1") (pintype "passive"))
      (node (ref "R1") (pin "2") (pinfunction "2_2") (pintype "passive"))
    )
    (net (code "49") (name "Net-(D4-A)") (class "Default")
      (node (ref "D4") (pin "1") (pinfunction "A_1") (pintype "passive"))
      (node (ref "R23") (pin "2") (pinfunction "2_2") (pintype "passive"))
    )
    (net (code "50") (name "Net-(D5-K)") (class "Default")
      (node (ref "D5") (pin "2") (pinfunction "K_2") (pintype "passive"))
      (node (ref "L1") (pin "1") (pinfunction "1_1") (pintype "passive"))
      (node (ref "U11") (pin "2") (pinfunction "OUT_2") (pintype "passive"))
    )
    (net (code "51") (name "Net-(P1-Pad2)") (class "Default")
      (node (ref "P1") (pin "2") (pinfunction "2_2") (pintype "passive"))
      (node (ref "S1") (pin "2") (pinfunction "2_2") (pintype "passive"))
    )
    (net (code "52") (name "Net-(P3-BS1)") (class "Default")
      (node (ref "P3") (pin "11") (pinfunction "BS1_11") (pintype "passive"))
      (node (ref "R26") (pin "1") (pinfunction "1_1") (pintype "passive"))
    )
    (net (code "53") (name "Net-(P3-C1N)") (class "Default")
      (node (ref "C31") (pin "1") (pinfunction "1_1") (pintype "passive"))
      (node (ref "P3") (pin "5") (pinfunction "C1N_5") (pintype "passive"))
    )
    (net (code "54") (name "Net-(P3-C1P)") (class "Default")
      (node (ref "C31") (pin "2") (pinfunction "2_2") (pintype "passive"))
      (node (ref "P3") (pin "4") (pinfunction "C1P_4") (pintype "passive"))
    )
    (net (code "55") (name "Net-(P3-C2N)") (class "Default")
      (node (ref "C32") (pin "1") (pinfunction "1_1") (pintype "passive"))
      (node (ref "P3") (pin "3") (pinfunction "C2N_3") (pintype "passive"))
    )
    (net (code "56") (name "Net-(P3-C2P)") (class "Default")
      (node (ref "C32") (pin "2") (pinfunction "2_2") (pintype "passive"))
      (node (ref "P3") (pin "2") (pinfunction "C2P_2") (pintype "passive"))
    )
    (net (code "57") (name "Net-(P3-IREF)") (class "Default")
      (node (ref "P3") (pin "26") (pinfunction "IREF_26") (pintype "passive"))
      (node (ref "R21") (pin "1") (pinfunction "1_1") (pintype "passive"))
    )
    (net (code "58") (name "Net-(P3-RES#)") (class "Default")
      (node (ref "C35") (pin "2") (pinfunction "2_2") (pintype "passive"))
      (node (ref "P3") (pin "14") (pinfunction "RES#_14") (pintype "passive"))
      (node (ref "R27") (pin "2") (pinfunction "2_2") (pintype "passive"))
    )
    (net (code "59") (name "Net-(P3-VCC)") (class "Default")
      (node (ref "C29") (pin "2") (pinfunction "2_2") (pintype "passive"))
      (node (ref "P3") (pin "28") (pinfunction "VCC_28") (pintype "passive"))
    )
    (net (code "60") (name "Net-(P3-VCOMH)") (class "Default")
      (node (ref "C30") (pin "2") (pinfunction "2_2") (pintype "passive"))
      (node (ref "P3") (pin "27") (pinfunction "VCOMH_27") (pintype "passive"))
    )
    (net (code "61") (name "Net-(Q1-B)") (class "Default")
      (node (ref "Q1") (pin "1") (pinfunction "B_1") (pintype "passive"))
      (node (ref "R4") (pin "2") (pinfunction "2_2") (pintype "passive"))
    )
    (net (code "62") (name "Net-(Q1-C)") (class "Default")
      (node (ref "Q1") (pin "3") (pinfunction "C_3") (pintype "passive"))
      (node (ref "U3") (pin "1") (pinfunction "+_1") (pintype "passive"))
    )
    (net (code "63") (name "Net-(U5-Motor+)") (class "Default")
      (node (ref "U5") (pin "1") (pinfunction "Motor+_1") (pintype "passive"))
      (node (ref "U6") (pin "1") (pinfunction "AO1_1") (pintype "passive"))
      (node (ref "U6") (pin "2") (pinfunction "AO1_2") (pintype "passive"))
    )
    (net (code "64") (name "Net-(U5-Motor-)") (class "Default")
      (node (ref "U5") (pin "6") (pinfunction "Motor-_6") (pintype "passive"))
      (node (ref "U6") (pin "5") (pinfunction "AO2_5") (pintype "passive"))
      (node (ref "U6") (pin "6") (pinfunction "AO2_6") (pintype "passive"))
    )
    (net (code "65") (name "Net-(U7-Motor+)") (class "Default")
      (node (ref "U6") (pin "7") (pinfunction "BO2_7") (pintype "passive"))
      (node (ref "U6") (pin "8") (pinfunction "BO2_8") (pintype "passive"))
      (node (ref "U7") (pin "1") (pinfunction "Motor+_1") (pintype "passive"))
    )
    (net (code "66") (name "Net-(U7-Motor-)") (class "Default")
      (node (ref "U6") (pin "11") (pinfunction "BO1_11") (pintype "passive"))
      (node (ref "U6") (pin "12") (pinfunction "BO1_12") (pintype "passive"))
      (node (ref "U7") (pin "6") (pinfunction "Motor-_6") (pintype "passive"))
    )
    (net (code "67") (name "Net-(U8-P1.2)") (class "Default")
      (node (ref "S7") (pin "1") (pinfunction "1_1") (pintype "passive"))
      (node (ref "U8") (pin "18") (pinfunction "P1.2_18") (pintype "passive"))
    )
    (net (code "68") (name "Net-(U9-UD+)") (class "Default")
      (node (ref "U9") (pin "5") (pinfunction "UD+_5") (pintype "passive"))
      (node (ref "USART1") (pin "3") (pinfunction "UD+_3") (pintype "passive"))
    )
    (net (code "69") (name "Net-(U9-UD-)") (class "Default")
      (node (ref "U9") (pin "6") (pinfunction "UD-_6") (pintype "passive"))
      (node (ref "USART1") (pin "2") (pinfunction "UD-_2") (pintype "passive"))
    )
    (net (code "70") (name "Net-(U9-V3)") (class "Default")
      (node (ref "C33") (pin "2") (pinfunction "2_2") (pintype "passive"))
      (node (ref "U9") (pin "4") (pinfunction "V3_4") (pintype "passive"))
    )
    (net (code "71") (name "Net-(U9-XI)") (class "Default")
      (node (ref "C34") (pin "2") (pinfunction "2_2") (pintype "passive"))
      (node (ref "U9") (pin "7") (pinfunction "XI_7") (pintype "passive"))
      (node (ref "Y2") (pin "2") (pinfunction "OSC2_2") (pintype "passive"))
    )
    (net (code "72") (name "Net-(U9-XO)") (class "Default")
      (node (ref "C28") (pin "2") (pinfunction "2_2") (pintype "passive"))
      (node (ref "U9") (pin "8") (pinfunction "XO_8") (pintype "passive"))
      (node (ref "Y2") (pin "1") (pinfunction "OSC1_1") (pintype "passive"))
    )
    (net (code "73") (name "VCC_3v3") (class "Default")
      (node (ref "C19") (pin "2") (pinfunction "2_2") (pintype "passive"))
      (node (ref "C20") (pin "2") (pinfunction "2_2") (pintype "passive"))
      (node (ref "C21") (pin "2") (pinfunction "2_2") (pintype "passive"))
      (node (ref "C22") (pin "2") (pinfunction "2_2") (pintype "passive"))
      (node (ref "C23") (pin "2") (pinfunction "2_2") (pintype "passive"))
      (node (ref "C24") (pin "2") (pinfunction "2_2") (pintype "passive"))
      (node (ref "C25") (pin "2") (pinfunction "2_2") (pintype "passive"))
      (node (ref "C26") (pin "1") (pinfunction "1_1") (pintype "passive"))
      (node (ref "C27") (pin "1") (pinfunction "1_1") (pintype "passive"))
      (node (ref "F1") (pin "2") (pinfunction "2_2") (pintype "passive"))
      (node (ref "R10") (pin "2") (pinfunction "2_2") (pintype "passive"))
      (node (ref "R11") (pin "2") (pinfunction "2_2") (pintype "passive"))
      (node (ref "R12") (pin "2") (pinfunction "2_2") (pintype "passive"))
      (node (ref "R13") (pin "2") (pinfunction "2_2") (pintype "passive"))
      (node (ref "R14") (pin "2") (pinfunction "2_2") (pintype "passive"))
      (node (ref "R17") (pin "2") (pinfunction "2_2") (pintype "passive"))
      (node (ref "R18") (pin "2") (pinfunction "2_2") (pintype "passive"))
      (node (ref "R19") (pin "2") (pinfunction "2_2") (pintype "passive"))
      (node (ref "R20") (pin "2") (pinfunction "2_2") (pintype "passive"))
      (node (ref "R7") (pin "2") (pinfunction "2_2") (pintype "passive"))
      (node (ref "R8") (pin "2") (pinfunction "2_2") (pintype "passive"))
      (node (ref "S7") (pin "2") (pinfunction "2_2") (pintype "passive"))
      (node (ref "U10") (pin "1") (pinfunction "Vref_1") (pintype "passive"))
      (node (ref "U10") (pin "2") (pinfunction "3.3V_2") (pintype "passive"))
      (node (ref "U2") (pin "24") (pinfunction "VDD_1_24") (pintype "passive"))
      (node (ref "U2") (pin "36") (pinfunction "VDD_2_36") (pintype "passive"))
      (node (ref "U2") (pin "48") (pinfunction "VDD_3_48") (pintype "passive"))
      (node (ref "U2") (pin "9") (pinfunction "VDDA_9") (pintype "passive"))
      (node (ref "U8") (pin "12") (pinfunction "3.3V_12") (pintype "passive"))
      (node (ref "U8") (pin "27") (pinfunction "3V3_27") (pintype "passive"))
    )
    (net (code "74") (name "VCC_5v") (class "Default")
      (node (ref "C1") (pin "1") (pinfunction "1_1") (pintype "passive"))
      (node (ref "C11") (pin "2") (pinfunction "2_2") (pintype "passive"))
      (node (ref "C12") (pin "2") (pinfunction "2_2") (pintype "passive"))
      (node (ref "C16") (pin "2") (pinfunction "2_2") (pintype "passive"))
      (node (ref "C17") (pin "2") (pinfunction "2_2") (pintype "passive"))
      (node (ref "C36") (pin "1") (pinfunction "1_1") (pintype "passive"))
      (node (ref "C37") (pin "2") (pinfunction "2_2") (pintype "passive"))
      (node (ref "C40") (pin "2") (pinfunction "2_2") (pintype "passive"))
      (node (ref "C7") (pin "1") (pinfunction "1_1") (pintype "passive"))
      (node (ref "L1") (pin "2") (pinfunction "2_2") (pintype "passive"))
      (node (ref "P2") (pin "1") (pinfunction "1_1") (pintype "passive"))
      (node (ref "Q1") (pin "2") (pinfunction "E_2") (pintype "passive"))
      (node (ref "R23") (pin "1") (pinfunction "1_1") (pintype "passive"))
      (node (ref "U1") (pin "1") (pinfunction "VCC_1") (pintype "passive"))
      (node (ref "U11") (pin "4") (pinfunction "FB_4") (pintype "passive"))
      (node (ref "U12") (pin "3") (pinfunction "VDD_3") (pintype "passive"))
      (node (ref "U4") (pin "3") (pinfunction "IN_3") (pintype "passive"))
      (node (ref "U5") (pin "2") (pinfunction "VCC_2") (pintype "passive"))
      (node (ref "U6") (pin "19") (pinfunction "STBY_19") (pintype "passive"))
      (node (ref "U6") (pin "20") (pinfunction "VCC_20") (pintype "passive"))
      (node (ref "U7") (pin "2") (pinfunction "VCC_2") (pintype "passive"))
      (node (ref "U9") (pin "16") (pinfunction "VCC_16") (pintype "passive"))
      (node (ref "USART1") (pin "1") (pinfunction "+5V_1") (pintype "passive"))
    )
    (net (code "75") (name "unconnected-(P3-NC-Pad7)") (class "Default")
      (node (ref "P3") (pin "7") (pinfunction "NC_7") (pintype "passive"))
    )
    (net (code "76") (name "unconnected-(S1-Pad3)") (class "Default")
      (node (ref "S1") (pin "3") (pinfunction "3_3") (pintype "passive"))
    )
    (net (code "77") (name "unconnected-(U1-ADO-Pad7)") (class "Default")
      (node (ref "U1") (pin "7") (pinfunction "ADO_7") (pintype "passive"))
    )
    (net (code "78") (name "unconnected-(U1-XCL-Pad6)") (class "Default")
      (node (ref "U1") (pin "6") (pinfunction "XCL_6") (pintype "passive"))
    )
    (net (code "79") (name "unconnected-(U1-XDA-Pad5)") (class "Default")
      (node (ref "U1") (pin "5") (pinfunction "XDA_5") (pintype "passive"))
    )
    (net (code "80") (name "unconnected-(U8-DC-Pad6)") (class "Default")
      (node (ref "U8") (pin "6") (pinfunction "DC_6") (pintype "passive"))
    )
    (net (code "81") (name "unconnected-(U8-DD-Pad7)") (class "Default")
      (node (ref "U8") (pin "7") (pinfunction "DD_7") (pintype "passive"))
    )
    (net (code "82") (name "unconnected-(U8-LEDCON-Pad14)") (class "Default")
      (node (ref "U8") (pin "14") (pinfunction "LEDCON_14") (pintype "passive"))
    )
    (net (code "83") (name "unconnected-(U8-NC-Pad3)") (class "Default")
      (node (ref "U8") (pin "3") (pinfunction "NC_3") (pintype "passive"))
    )
    (net (code "84") (name "unconnected-(U8-NC-Pad4)") (class "Default")
      (node (ref "U8") (pin "4") (pinfunction "NC_4") (pintype "passive"))
    )
    (net (code "85") (name "unconnected-(U8-NC-Pad5)") (class "Default")
      (node (ref "U8") (pin "5") (pinfunction "NC_5") (pintype "passive"))
    )
    (net (code "86") (name "unconnected-(U8-P0.0-Pad26)") (class "Default")
      (node (ref "U8") (pin "26") (pinfunction "P0.0_26") (pintype "passive"))
    )
    (net (code "87") (name "unconnected-(U8-P0.1-Pad24)") (class "Default")
      (node (ref "U8") (pin "24") (pinfunction "P0.1_24") (pintype "passive"))
    )
    (net (code "88") (name "unconnected-(U8-P0.6-Pad23)") (class "Default")
      (node (ref "U8") (pin "23") (pinfunction "P0.6_23") (pintype "passive"))
    )
    (net (code "89") (name "unconnected-(U8-P0.7-Pad20)") (class "Default")
      (node (ref "U8") (pin "20") (pinfunction "P0.7_20") (pintype "passive"))
    )
    (net (code "90") (name "unconnected-(U8-P1.0-Pad19)") (class "Default")
      (node (ref "U8") (pin "19") (pinfunction "P1.0_19") (pintype "passive"))
    )
    (net (code "91") (name "unconnected-(U8-P1.3-Pad16)") (class "Default")
      (node (ref "U8") (pin "16") (pinfunction "P1.3_16") (pintype "passive"))
    )
    (net (code "92") (name "unconnected-(U8-P1.4-Pad15)") (class "Default")
      (node (ref "U8") (pin "15") (pinfunction "P1.4_15") (pintype "passive"))
    )
    (net (code "93") (name "unconnected-(U8-P1.5-Pad25)") (class "Default")
      (node (ref "U8") (pin "25") (pinfunction "P1.5_25") (pintype "passive"))
    )
    (net (code "94") (name "unconnected-(U8-P1.6-Pad10)") (class "Default")
      (node (ref "U8") (pin "10") (pinfunction "P1.6_10") (pintype "passive"))
    )
    (net (code "95") (name "unconnected-(U8-P1.7-Pad9)") (class "Default")
      (node (ref "U8") (pin "9") (pinfunction "P1.7_9") (pintype "passive"))
    )
    (net (code "96") (name "unconnected-(U8-P2.0-Pad8)") (class "Default")
      (node (ref "U8") (pin "8") (pinfunction "P2.0_8") (pintype "passive"))
    )
    (net (code "97") (name "unconnected-(U8-RST-Pad11)") (class "Default")
      (node (ref "U8") (pin "11") (pinfunction "RST_11") (pintype "passive"))
    )
    (net (code "98") (name "unconnected-(U8-USB_D+-Pad22)") (class "Default")
      (node (ref "U8") (pin "22") (pinfunction "USB_D+_22") (pintype "passive"))
    )
    (net (code "99") (name "unconnected-(U8-USB_D--Pad21)") (class "Default")
      (node (ref "U8") (pin "21") (pinfunction "USB_D-_21") (pintype "passive"))
    )
    (net (code "100") (name "unconnected-(U9-CTS#-Pad9)") (class "Default")
      (node (ref "U9") (pin "9") (pinfunction "CTS#_9") (pintype "passive"))
    )
    (net (code "101") (name "unconnected-(U9-DCD#-Pad12)") (class "Default")
      (node (ref "U9") (pin "12") (pinfunction "DCD#_12") (pintype "passive"))
    )
    (net (code "102") (name "unconnected-(U9-DSR#-Pad10)") (class "Default")
      (node (ref "U9") (pin "10") (pinfunction "DSR#_10") (pintype "passive"))
    )
    (net (code "103") (name "unconnected-(U9-DTR#-Pad13)") (class "Default")
      (node (ref "U9") (pin "13") (pinfunction "DTR#_13") (pintype "passive"))
    )
    (net (code "104") (name "unconnected-(U9-R232-Pad15)") (class "Default")
      (node (ref "U9") (pin "15") (pinfunction "R232_15") (pintype "passive"))
    )
    (net (code "105") (name "unconnected-(U9-RI#-Pad11)") (class "Default")
      (node (ref "U9") (pin "11") (pinfunction "RI#_11") (pintype "passive"))
    )
    (net (code "106") (name "unconnected-(U9-RTS#-Pad14)") (class "Default")
      (node (ref "U9") (pin "14") (pinfunction "RTS#_14") (pintype "passive"))
    )
  )
)
